# testboard.net
KiCad netlist of a schematic drawn in EasyEDA Pro
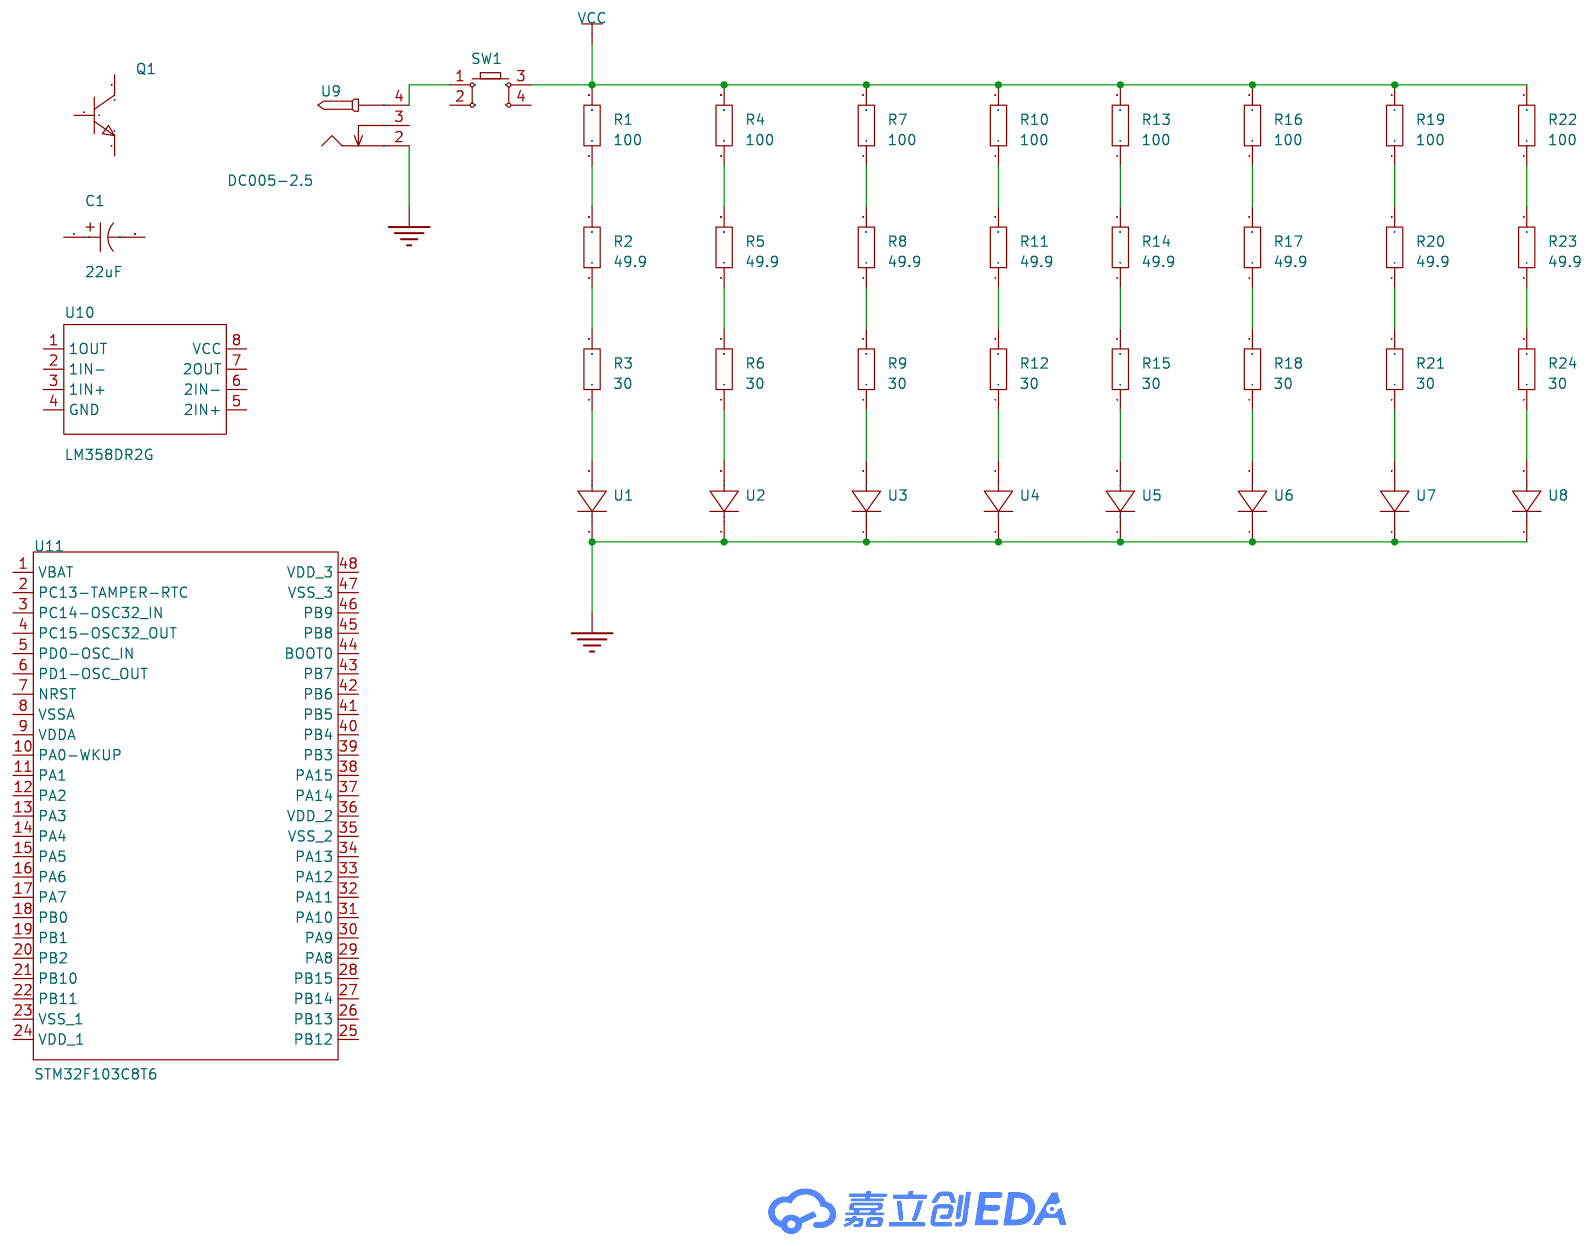
[diagram p0: schematic sheet]

(export (version "E")
  (design (tool "Eeschema 10.0.6"))
  (components
    (comp (ref "C1")
      (value "22uF")
      (footprint "easyedapro:CAP-SMD_BD5.0-L5.3-W5.3-FD")
      (description "容值:22uF;额定电压:25V;")
      (fields (field (name "Manufacturer Part") "RYHV25V22UF5*8") (field (name "Manufacturer") "HONOR(荣誉)"))
      (libsource (lib "easyedapro") (part "RYHV25V22UF5*8"))
    )
    (comp (ref "Q1")
      (value "~")
      (footprint "easyedapro:S8050_SOT-23")
      (libsource (lib "easyedapro") (part "NPN"))
    )
    (comp (ref "R1") (value "100") (footprint "easyedapro:R0603") (libsource (lib "easyedapro") (part "电阻")))
    (comp (ref "R2") (value "49.9") (footprint "easyedapro:R0603") (libsource (lib "easyedapro") (part "电阻")))
    (comp (ref "R3") (value "30") (footprint "easyedapro:R0603") (libsource (lib "easyedapro") (part "电阻")))
    (comp (ref "R4") (value "100") (footprint "easyedapro:R0603") (libsource (lib "easyedapro") (part "电阻")))
    (comp (ref "R5") (value "49.9") (footprint "easyedapro:R0603") (libsource (lib "easyedapro") (part "电阻")))
    (comp (ref "R6") (value "30") (footprint "easyedapro:R0603") (libsource (lib "easyedapro") (part "电阻")))
    (comp (ref "R7") (value "100") (footprint "easyedapro:R0603") (libsource (lib "easyedapro") (part "电阻")))
    (comp (ref "R8") (value "49.9") (footprint "easyedapro:R0603") (libsource (lib "easyedapro") (part "电阻")))
    (comp (ref "R9") (value "30") (footprint "easyedapro:R0603") (libsource (lib "easyedapro") (part "电阻")))
    (comp (ref "R10") (value "100") (footprint "easyedapro:R0603") (libsource (lib "easyedapro") (part "电阻")))
    (comp (ref "R11")
      (value "49.9")
      (footprint "easyedapro:R0603")
      (libsource (lib "easyedapro") (part "电阻"))
    )
    (comp (ref "R12") (value "30") (footprint "easyedapro:R0603") (libsource (lib "easyedapro") (part "电阻")))
    (comp (ref "R13") (value "100") (footprint "easyedapro:R0603") (libsource (lib "easyedapro") (part "电阻")))
    (comp (ref "R14")
      (value "49.9")
      (footprint "easyedapro:R0603")
      (libsource (lib "easyedapro") (part "电阻"))
    )
    (comp (ref "R15") (value "30") (footprint "easyedapro:R0603") (libsource (lib "easyedapro") (part "电阻")))
    (comp (ref "R16") (value "100") (footprint "easyedapro:R0603") (libsource (lib "easyedapro") (part "电阻")))
    (comp (ref "R17")
      (value "49.9")
      (footprint "easyedapro:R0603")
      (libsource (lib "easyedapro") (part "电阻"))
    )
    (comp (ref "R18") (value "30") (footprint "easyedapro:R0603") (libsource (lib "easyedapro") (part "电阻")))
    (comp (ref "R19") (value "100") (footprint "easyedapro:R0603") (libsource (lib "easyedapro") (part "电阻")))
    (comp (ref "R20")
      (value "49.9")
      (footprint "easyedapro:R0603")
      (libsource (lib "easyedapro") (part "电阻"))
    )
    (comp (ref "R21") (value "30") (footprint "easyedapro:R0603") (libsource (lib "easyedapro") (part "电阻")))
    (comp (ref "R22") (value "100") (footprint "easyedapro:R0603") (libsource (lib "easyedapro") (part "电阻")))
    (comp (ref "R23")
      (value "49.9")
      (footprint "easyedapro:R0603")
      (libsource (lib "easyedapro") (part "电阻"))
    )
    (comp (ref "R24") (value "30") (footprint "easyedapro:R0603") (libsource (lib "easyedapro") (part "电阻")))
    (comp (ref "SW1")
      (value "~")
      (footprint "easyedapro:SW-SMD_4P-L6.0-W6.0-P4.50-LS9.0-2")
      (libsource (lib "easyedapro") (part "轻触按键"))
    )
    (comp (ref "U1")
      (value "LTST-C190YKT")
      (footprint "easyedapro:SMA_L4.3-W2.6-LS5.1-RD")
      (fields (field (name "Manufacturer") "LITEON(光宝)"))
      (libsource (lib "easyedapro") (part "1N4007_C9900004759"))
    )
    (comp (ref "U2")
      (value "LTST-C190YKT")
      (footprint "easyedapro:SMA_L4.3-W2.6-LS5.1-RD")
      (fields (field (name "Manufacturer") "LITEON(光宝)"))
      (libsource (lib "easyedapro") (part "1N4007_C9900004759"))
    )
    (comp (ref "U3")
      (value "LTST-C190YKT")
      (footprint "easyedapro:SMA_L4.3-W2.6-LS5.1-RD")
      (fields (field (name "Manufacturer") "LITEON(光宝)"))
      (libsource (lib "easyedapro") (part "1N4007_C9900004759"))
    )
    (comp (ref "U4")
      (value "LTST-C190YKT")
      (footprint "easyedapro:SMA_L4.3-W2.6-LS5.1-RD")
      (fields (field (name "Manufacturer") "LITEON(光宝)"))
      (libsource (lib "easyedapro") (part "1N4007_C9900004759"))
    )
    (comp (ref "U5")
      (value "LTST-C190YKT")
      (footprint "easyedapro:SMA_L4.3-W2.6-LS5.1-RD")
      (fields (field (name "Manufacturer") "LITEON(光宝)"))
      (libsource (lib "easyedapro") (part "1N4007_C9900004759"))
    )
    (comp (ref "U6")
      (value "LTST-C190YKT")
      (footprint "easyedapro:SMA_L4.3-W2.6-LS5.1-RD")
      (fields (field (name "Manufacturer") "LITEON(光宝)"))
      (libsource (lib "easyedapro") (part "1N4007_C9900004759"))
    )
    (comp (ref "U7")
      (value "LTST-C190YKT")
      (footprint "easyedapro:SMA_L4.3-W2.6-LS5.1-RD")
      (fields (field (name "Manufacturer") "LITEON(光宝)"))
      (libsource (lib "easyedapro") (part "1N4007_C9900004759"))
    )
    (comp (ref "U8")
      (value "LTST-C190YKT")
      (footprint "easyedapro:SMA_L4.3-W2.6-LS5.1-RD")
      (fields (field (name "Manufacturer") "LITEON(光宝)"))
      (libsource (lib "easyedapro") (part "1N4007_C9900004759"))
    )
    (comp (ref "U9")
      (value "DC005-2.5")
      (footprint "easyedapro:DC-IN-TH_DC005-2.5MM")
      (description "连接器类型:DC电源插座;安装方式:弯插;触点内径:2.5mm;触点外径:6.3mm;额定电流:500mA;额定电压:30V;工作温度范围:-25°C~+70°C;")
      (fields (field (name "Manufacturer") "SHOU HAN(首韩)"))
      (libsource (lib "easyedapro") (part "DC005-2.5"))
    )
    (comp (ref "U10")
      (value "LM358DR2G")
      (footprint "easyedapro:SOIC-8_L5.0-W4.0-P1.27-LS6.0-BL")
      (description "放大器数:双路;轨到轨:-;增益带宽积(GBP):-;输入失调电压(Vos):7mV;压摆率(SR):-;输入偏置电流(Ib):150nA;")
      (fields (field (name "Manufacturer") "onsemi(安森美)"))
      (libsource (lib "easyedapro") (part "LM358DR2G"))
    )
    (comp (ref "U11")
      (value "STM32F103C8T6")
      (footprint "easyedapro:LQFP-48_L7.0-W7.0-P0.50-LS9.0-BL")
      (description "CPU内核:ARM-M3;CPU最大主频:72MHz;应用领域:-;")
      (fields (field (name "Manufacturer") "ST(意法半导体)"))
      (libsource (lib "easyedapro") (part "STM32F103C8T6"))
    )
  )
  (nets
    (net (code "1") (name "GND") (class "Default")
      (node (ref "U1") (pin "1") (pinfunction "K_1") (pintype "unspecified"))
      (node (ref "U2") (pin "1") (pinfunction "K_1") (pintype "unspecified"))
      (node (ref "U3") (pin "1") (pinfunction "K_1") (pintype "unspecified"))
      (node (ref "U4") (pin "1") (pinfunction "K_1") (pintype "unspecified"))
      (node (ref "U5") (pin "1") (pinfunction "K_1") (pintype "unspecified"))
      (node (ref "U6") (pin "1") (pinfunction "K_1") (pintype "unspecified"))
      (node (ref "U7") (pin "1") (pinfunction "K_1") (pintype "unspecified"))
      (node (ref "U8") (pin "1") (pinfunction "K_1") (pintype "unspecified"))
      (node (ref "U9") (pin "2") (pinfunction "2_2") (pintype "unspecified"))
    )
    (net (code "2") (name "Net-(R1-Pad1)") (class "Default")
      (node (ref "R1") (pin "1") (pinfunction "1_1") (pintype "input"))
      (node (ref "R2") (pin "2") (pinfunction "2_2") (pintype "input"))
    )
    (net (code "3") (name "Net-(R2-Pad1)") (class "Default")
      (node (ref "R2") (pin "1") (pinfunction "1_1") (pintype "input"))
      (node (ref "R3") (pin "2") (pinfunction "2_2") (pintype "input"))
    )
    (net (code "4") (name "Net-(R4-Pad1)") (class "Default")
      (node (ref "R4") (pin "1") (pinfunction "1_1") (pintype "input"))
      (node (ref "R5") (pin "2") (pinfunction "2_2") (pintype "input"))
    )
    (net (code "5") (name "Net-(R5-Pad1)") (class "Default")
      (node (ref "R5") (pin "1") (pinfunction "1_1") (pintype "input"))
      (node (ref "R6") (pin "2") (pinfunction "2_2") (pintype "input"))
    )
    (net (code "6") (name "Net-(R7-Pad1)") (class "Default")
      (node (ref "R7") (pin "1") (pinfunction "1_1") (pintype "input"))
      (node (ref "R8") (pin "2") (pinfunction "2_2") (pintype "input"))
    )
    (net (code "7") (name "Net-(R8-Pad1)") (class "Default")
      (node (ref "R8") (pin "1") (pinfunction "1_1") (pintype "input"))
      (node (ref "R9") (pin "2") (pinfunction "2_2") (pintype "input"))
    )
    (net (code "8") (name "Net-(R10-Pad1)") (class "Default")
      (node (ref "R10") (pin "1") (pinfunction "1_1") (pintype "input"))
      (node (ref "R11") (pin "2") (pinfunction "2_2") (pintype "input"))
    )
    (net (code "9") (name "Net-(R11-Pad1)") (class "Default")
      (node (ref "R11") (pin "1") (pinfunction "1_1") (pintype "input"))
      (node (ref "R12") (pin "2") (pinfunction "2_2") (pintype "input"))
    )
    (net (code "10") (name "Net-(R13-Pad1)") (class "Default")
      (node (ref "R13") (pin "1") (pinfunction "1_1") (pintype "input"))
      (node (ref "R14") (pin "2") (pinfunction "2_2") (pintype "input"))
    )
    (net (code "11") (name "Net-(R14-Pad1)") (class "Default")
      (node (ref "R14") (pin "1") (pinfunction "1_1") (pintype "input"))
      (node (ref "R15") (pin "2") (pinfunction "2_2") (pintype "input"))
    )
    (net (code "12") (name "Net-(R16-Pad1)") (class "Default")
      (node (ref "R16") (pin "1") (pinfunction "1_1") (pintype "input"))
      (node (ref "R17") (pin "2") (pinfunction "2_2") (pintype "input"))
    )
    (net (code "13") (name "Net-(R17-Pad1)") (class "Default")
      (node (ref "R17") (pin "1") (pinfunction "1_1") (pintype "input"))
      (node (ref "R18") (pin "2") (pinfunction "2_2") (pintype "input"))
    )
    (net (code "14") (name "Net-(R19-Pad1)") (class "Default")
      (node (ref "R19") (pin "1") (pinfunction "1_1") (pintype "input"))
      (node (ref "R20") (pin "2") (pinfunction "2_2") (pintype "input"))
    )
    (net (code "15") (name "Net-(R20-Pad1)") (class "Default")
      (node (ref "R20") (pin "1") (pinfunction "1_1") (pintype "input"))
      (node (ref "R21") (pin "2") (pinfunction "2_2") (pintype "input"))
    )
    (net (code "16") (name "Net-(R22-Pad1)") (class "Default")
      (node (ref "R22") (pin "1") (pinfunction "1_1") (pintype "input"))
      (node (ref "R23") (pin "2") (pinfunction "2_2") (pintype "input"))
    )
    (net (code "17") (name "Net-(R23-Pad1)") (class "Default")
      (node (ref "R23") (pin "1") (pinfunction "1_1") (pintype "input"))
      (node (ref "R24") (pin "2") (pinfunction "2_2") (pintype "input"))
    )
    (net (code "18") (name "Net-(SW1-Pad1)") (class "Default")
      (node (ref "SW1") (pin "1") (pinfunction "1_1") (pintype "input"))
      (node (ref "U9") (pin "4") (pinfunction "4_4") (pintype "unspecified"))
    )
    (net (code "19") (name "Net-(U1-A)") (class "Default")
      (node (ref "R3") (pin "1") (pinfunction "1_1") (pintype "input"))
      (node (ref "U1") (pin "2") (pinfunction "A_2") (pintype "unspecified"))
    )
    (net (code "20") (name "Net-(U2-A)") (class "Default")
      (node (ref "R6") (pin "1") (pinfunction "1_1") (pintype "input"))
      (node (ref "U2") (pin "2") (pinfunction "A_2") (pintype "unspecified"))
    )
    (net (code "21") (name "Net-(U3-A)") (class "Default")
      (node (ref "R9") (pin "1") (pinfunction "1_1") (pintype "input"))
      (node (ref "U3") (pin "2") (pinfunction "A_2") (pintype "unspecified"))
    )
    (net (code "22") (name "Net-(U4-A)") (class "Default")
      (node (ref "R12") (pin "1") (pinfunction "1_1") (pintype "input"))
      (node (ref "U4") (pin "2") (pinfunction "A_2") (pintype "unspecified"))
    )
    (net (code "23") (name "Net-(U5-A)") (class "Default")
      (node (ref "R15") (pin "1") (pinfunction "1_1") (pintype "input"))
      (node (ref "U5") (pin "2") (pinfunction "A_2") (pintype "unspecified"))
    )
    (net (code "24") (name "Net-(U6-A)") (class "Default")
      (node (ref "R18") (pin "1") (pinfunction "1_1") (pintype "input"))
      (node (ref "U6") (pin "2") (pinfunction "A_2") (pintype "unspecified"))
    )
    (net (code "25") (name "Net-(U7-A)") (class "Default")
      (node (ref "R21") (pin "1") (pinfunction "1_1") (pintype "input"))
      (node (ref "U7") (pin "2") (pinfunction "A_2") (pintype "unspecified"))
    )
    (net (code "26") (name "Net-(U8-A)") (class "Default")
      (node (ref "R24") (pin "1") (pinfunction "1_1") (pintype "input"))
      (node (ref "U8") (pin "2") (pinfunction "A_2") (pintype "unspecified"))
    )
    (net (code "27") (name "VCC") (class "Default")
      (node (ref "R1") (pin "2") (pinfunction "2_2") (pintype "input"))
      (node (ref "R10") (pin "2") (pinfunction "2_2") (pintype "input"))
      (node (ref "R13") (pin "2") (pinfunction "2_2") (pintype "input"))
      (node (ref "R16") (pin "2") (pinfunction "2_2") (pintype "input"))
      (node (ref "R19") (pin "2") (pinfunction "2_2") (pintype "input"))
      (node (ref "R22") (pin "2") (pinfunction "2_2") (pintype "input"))
      (node (ref "R4") (pin "2") (pinfunction "2_2") (pintype "input"))
      (node (ref "R7") (pin "2") (pinfunction "2_2") (pintype "input"))
      (node (ref "SW1") (pin "3") (pinfunction "3_3") (pintype "input"))
    )
    (net (code "28") (name "unconnected-(C1-Pad1)") (class "Default")
      (node (ref "C1") (pin "1") (pinfunction "1_1") (pintype "input"))
    )
    (net (code "29") (name "unconnected-(C1-Pad2)") (class "Default")
      (node (ref "C1") (pin "2") (pinfunction "2_2") (pintype "input"))
    )
    (net (code "30") (name "unconnected-(Q1-Pad1)") (class "Default")
      (node (ref "Q1") (pin "1") (pinfunction "1_1") (pintype "unspecified"))
    )
    (net (code "31") (name "unconnected-(Q1-Pad2)") (class "Default")
      (node (ref "Q1") (pin "2") (pinfunction "2_2") (pintype "unspecified"))
    )
    (net (code "32") (name "unconnected-(Q1-Pad3)") (class "Default")
      (node (ref "Q1") (pin "3") (pinfunction "3_3") (pintype "unspecified"))
    )
    (net (code "33") (name "unconnected-(SW1-Pad2)") (class "Default")
      (node (ref "SW1") (pin "2") (pinfunction "2_2") (pintype "input"))
    )
    (net (code "34") (name "unconnected-(SW1-Pad4)") (class "Default")
      (node (ref "SW1") (pin "4") (pinfunction "4_4") (pintype "input"))
    )
    (net (code "35") (name "unconnected-(U9-Pad3)") (class "Default")
      (node (ref "U9") (pin "3") (pinfunction "3_3") (pintype "unspecified"))
    )
    (net (code "36") (name "unconnected-(U10-1IN+-Pad3)") (class "Default")
      (node (ref "U10") (pin "3") (pinfunction "1IN+_3") (pintype "unspecified"))
    )
    (net (code "37") (name "unconnected-(U10-1IN--Pad2)") (class "Default")
      (node (ref "U10") (pin "2") (pinfunction "1IN-_2") (pintype "unspecified"))
    )
    (net (code "38") (name "unconnected-(U10-1OUT-Pad1)") (class "Default")
      (node (ref "U10") (pin "1") (pinfunction "1OUT_1") (pintype "unspecified"))
    )
    (net (code "39") (name "unconnected-(U10-2IN+-Pad5)") (class "Default")
      (node (ref "U10") (pin "5") (pinfunction "2IN+_5") (pintype "unspecified"))
    )
    (net (code "40") (name "unconnected-(U10-2IN--Pad6)") (class "Default")
      (node (ref "U10") (pin "6") (pinfunction "2IN-_6") (pintype "unspecified"))
    )
    (net (code "41") (name "unconnected-(U10-2OUT-Pad7)") (class "Default")
      (node (ref "U10") (pin "7") (pinfunction "2OUT_7") (pintype "unspecified"))
    )
    (net (code "42") (name "unconnected-(U10-GND-Pad4)") (class "Default")
      (node (ref "U10") (pin "4") (pinfunction "GND_4") (pintype "unspecified"))
    )
    (net (code "43") (name "unconnected-(U10-VCC-Pad8)") (class "Default")
      (node (ref "U10") (pin "8") (pinfunction "VCC_8") (pintype "unspecified"))
    )
    (net (code "44") (name "unconnected-(U11-BOOT0-Pad44)") (class "Default")
      (node (ref "U11") (pin "44") (pinfunction "BOOT0_44") (pintype "unspecified"))
    )
    (net (code "45") (name "unconnected-(U11-NRST-Pad7)") (class "Default")
      (node (ref "U11") (pin "7") (pinfunction "NRST_7") (pintype "unspecified"))
    )
    (net (code "46") (name "unconnected-(U11-PA0-WKUP-Pad10)") (class "Default")
      (node (ref "U11") (pin "10") (pinfunction "PA0-WKUP_10") (pintype "unspecified"))
    )
    (net (code "47") (name "unconnected-(U11-PA1-Pad11)") (class "Default")
      (node (ref "U11") (pin "11") (pinfunction "PA1_11") (pintype "unspecified"))
    )
    (net (code "48") (name "unconnected-(U11-PA2-Pad12)") (class "Default")
      (node (ref "U11") (pin "12") (pinfunction "PA2_12") (pintype "unspecified"))
    )
    (net (code "49") (name "unconnected-(U11-PA3-Pad13)") (class "Default")
      (node (ref "U11") (pin "13") (pinfunction "PA3_13") (pintype "unspecified"))
    )
    (net (code "50") (name "unconnected-(U11-PA4-Pad14)") (class "Default")
      (node (ref "U11") (pin "14") (pinfunction "PA4_14") (pintype "unspecified"))
    )
    (net (code "51") (name "unconnected-(U11-PA5-Pad15)") (class "Default")
      (node (ref "U11") (pin "15") (pinfunction "PA5_15") (pintype "unspecified"))
    )
    (net (code "52") (name "unconnected-(U11-PA6-Pad16)") (class "Default")
      (node (ref "U11") (pin "16") (pinfunction "PA6_16") (pintype "unspecified"))
    )
    (net (code "53") (name "unconnected-(U11-PA7-Pad17)") (class "Default")
      (node (ref "U11") (pin "17") (pinfunction "PA7_17") (pintype "unspecified"))
    )
    (net (code "54") (name "unconnected-(U11-PA8-Pad29)") (class "Default")
      (node (ref "U11") (pin "29") (pinfunction "PA8_29") (pintype "unspecified"))
    )
    (net (code "55") (name "unconnected-(U11-PA9-Pad30)") (class "Default")
      (node (ref "U11") (pin "30") (pinfunction "PA9_30") (pintype "unspecified"))
    )
    (net (code "56") (name "unconnected-(U11-PA10-Pad31)") (class "Default")
      (node (ref "U11") (pin "31") (pinfunction "PA10_31") (pintype "unspecified"))
    )
    (net (code "57") (name "unconnected-(U11-PA11-Pad32)") (class "Default")
      (node (ref "U11") (pin "32") (pinfunction "PA11_32") (pintype "unspecified"))
    )
    (net (code "58") (name "unconnected-(U11-PA12-Pad33)") (class "Default")
      (node (ref "U11") (pin "33") (pinfunction "PA12_33") (pintype "unspecified"))
    )
    (net (code "59") (name "unconnected-(U11-PA13-Pad34)") (class "Default")
      (node (ref "U11") (pin "34") (pinfunction "PA13_34") (pintype "unspecified"))
    )
    (net (code "60") (name "unconnected-(U11-PA14-Pad37)") (class "Default")
      (node (ref "U11") (pin "37") (pinfunction "PA14_37") (pintype "unspecified"))
    )
    (net (code "61") (name "unconnected-(U11-PA15-Pad38)") (class "Default")
      (node (ref "U11") (pin "38") (pinfunction "PA15_38") (pintype "unspecified"))
    )
    (net (code "62") (name "unconnected-(U11-PB0-Pad18)") (class "Default")
      (node (ref "U11") (pin "18") (pinfunction "PB0_18") (pintype "unspecified"))
    )
    (net (code "63") (name "unconnected-(U11-PB1-Pad19)") (class "Default")
      (node (ref "U11") (pin "19") (pinfunction "PB1_19") (pintype "unspecified"))
    )
    (net (code "64") (name "unconnected-(U11-PB2-Pad20)") (class "Default")
      (node (ref "U11") (pin "20") (pinfunction "PB2_20") (pintype "unspecified"))
    )
    (net (code "65") (name "unconnected-(U11-PB3-Pad39)") (class "Default")
      (node (ref "U11") (pin "39") (pinfunction "PB3_39") (pintype "unspecified"))
    )
    (net (code "66") (name "unconnected-(U11-PB4-Pad40)") (class "Default")
      (node (ref "U11") (pin "40") (pinfunction "PB4_40") (pintype "unspecified"))
    )
    (net (code "67") (name "unconnected-(U11-PB5-Pad41)") (class "Default")
      (node (ref "U11") (pin "41") (pinfunction "PB5_41") (pintype "unspecified"))
    )
    (net (code "68") (name "unconnected-(U11-PB6-Pad42)") (class "Default")
      (node (ref "U11") (pin "42") (pinfunction "PB6_42") (pintype "unspecified"))
    )
    (net (code "69") (name "unconnected-(U11-PB7-Pad43)") (class "Default")
      (node (ref "U11") (pin "43") (pinfunction "PB7_43") (pintype "unspecified"))
    )
    (net (code "70") (name "unconnected-(U11-PB8-Pad45)") (class "Default")
      (node (ref "U11") (pin "45") (pinfunction "PB8_45") (pintype "unspecified"))
    )
    (net (code "71") (name "unconnected-(U11-PB9-Pad46)") (class "Default")
      (node (ref "U11") (pin "46") (pinfunction "PB9_46") (pintype "unspecified"))
    )
    (net (code "72") (name "unconnected-(U11-PB10-Pad21)") (class "Default")
      (node (ref "U11") (pin "21") (pinfunction "PB10_21") (pintype "unspecified"))
    )
    (net (code "73") (name "unconnected-(U11-PB11-Pad22)") (class "Default")
      (node (ref "U11") (pin "22") (pinfunction "PB11_22") (pintype "unspecified"))
    )
    (net (code "74") (name "unconnected-(U11-PB12-Pad25)") (class "Default")
      (node (ref "U11") (pin "25") (pinfunction "PB12_25") (pintype "unspecified"))
    )
    (net (code "75") (name "unconnected-(U11-PB13-Pad26)") (class "Default")
      (node (ref "U11") (pin "26") (pinfunction "PB13_26") (pintype "unspecified"))
    )
    (net (code "76") (name "unconnected-(U11-PB14-Pad27)") (class "Default")
      (node (ref "U11") (pin "27") (pinfunction "PB14_27") (pintype "unspecified"))
    )
    (net (code "77") (name "unconnected-(U11-PB15-Pad28)") (class "Default")
      (node (ref "U11") (pin "28") (pinfunction "PB15_28") (pintype "unspecified"))
    )
    (net (code "78") (name "unconnected-(U11-PC13-TAMPER-RTC-Pad2)") (class "Default")
      (node (ref "U11") (pin "2") (pinfunction "PC13-TAMPER-RTC_2") (pintype "unspecified"))
    )
    (net (code "79") (name "unconnected-(U11-PC14-OSC32_IN-Pad3)") (class "Default")
      (node (ref "U11") (pin "3") (pinfunction "PC14-OSC32_IN_3") (pintype "unspecified"))
    )
    (net (code "80") (name "unconnected-(U11-PC15-OSC32_OUT-Pad4)") (class "Default")
      (node (ref "U11") (pin "4") (pinfunction "PC15-OSC32_OUT_4") (pintype "unspecified"))
    )
    (net (code "81") (name "unconnected-(U11-PD0-OSC_IN-Pad5)") (class "Default")
      (node (ref "U11") (pin "5") (pinfunction "PD0-OSC_IN_5") (pintype "unspecified"))
    )
    (net (code "82") (name "unconnected-(U11-PD1-OSC_OUT-Pad6)") (class "Default")
      (node (ref "U11") (pin "6") (pinfunction "PD1-OSC_OUT_6") (pintype "unspecified"))
    )
    (net (code "83") (name "unconnected-(U11-VBAT-Pad1)") (class "Default")
      (node (ref "U11") (pin "1") (pinfunction "VBAT_1") (pintype "unspecified"))
    )
    (net (code "84") (name "unconnected-(U11-VDDA-Pad9)") (class "Default")
      (node (ref "U11") (pin "9") (pinfunction "VDDA_9") (pintype "unspecified"))
    )
    (net (code "85") (name "unconnected-(U11-VDD_1-Pad24)") (class "Default")
      (node (ref "U11") (pin "24") (pinfunction "VDD_1_24") (pintype "unspecified"))
    )
    (net (code "86") (name "unconnected-(U11-VDD_2-Pad36)") (class "Default")
      (node (ref "U11") (pin "36") (pinfunction "VDD_2_36") (pintype "unspecified"))
    )
    (net (code "87") (name "unconnected-(U11-VDD_3-Pad48)") (class "Default")
      (node (ref "U11") (pin "48") (pinfunction "VDD_3_48") (pintype "unspecified"))
    )
    (net (code "88") (name "unconnected-(U11-VSSA-Pad8)") (class "Default")
      (node (ref "U11") (pin "8") (pinfunction "VSSA_8") (pintype "unspecified"))
    )
    (net (code "89") (name "unconnected-(U11-VSS_1-Pad23)") (class "Default")
      (node (ref "U11") (pin "23") (pinfunction "VSS_1_23") (pintype "unspecified"))
    )
    (net (code "90") (name "unconnected-(U11-VSS_2-Pad35)") (class "Default")
      (node (ref "U11") (pin "35") (pinfunction "VSS_2_35") (pintype "unspecified"))
    )
    (net (code "91") (name "unconnected-(U11-VSS_3-Pad47)") (class "Default")
      (node (ref "U11") (pin "47") (pinfunction "VSS_3_47") (pintype "unspecified"))
    )
  )
)
